# Genesis.net
KiCad netlist of a schematic drawn in EAGLE
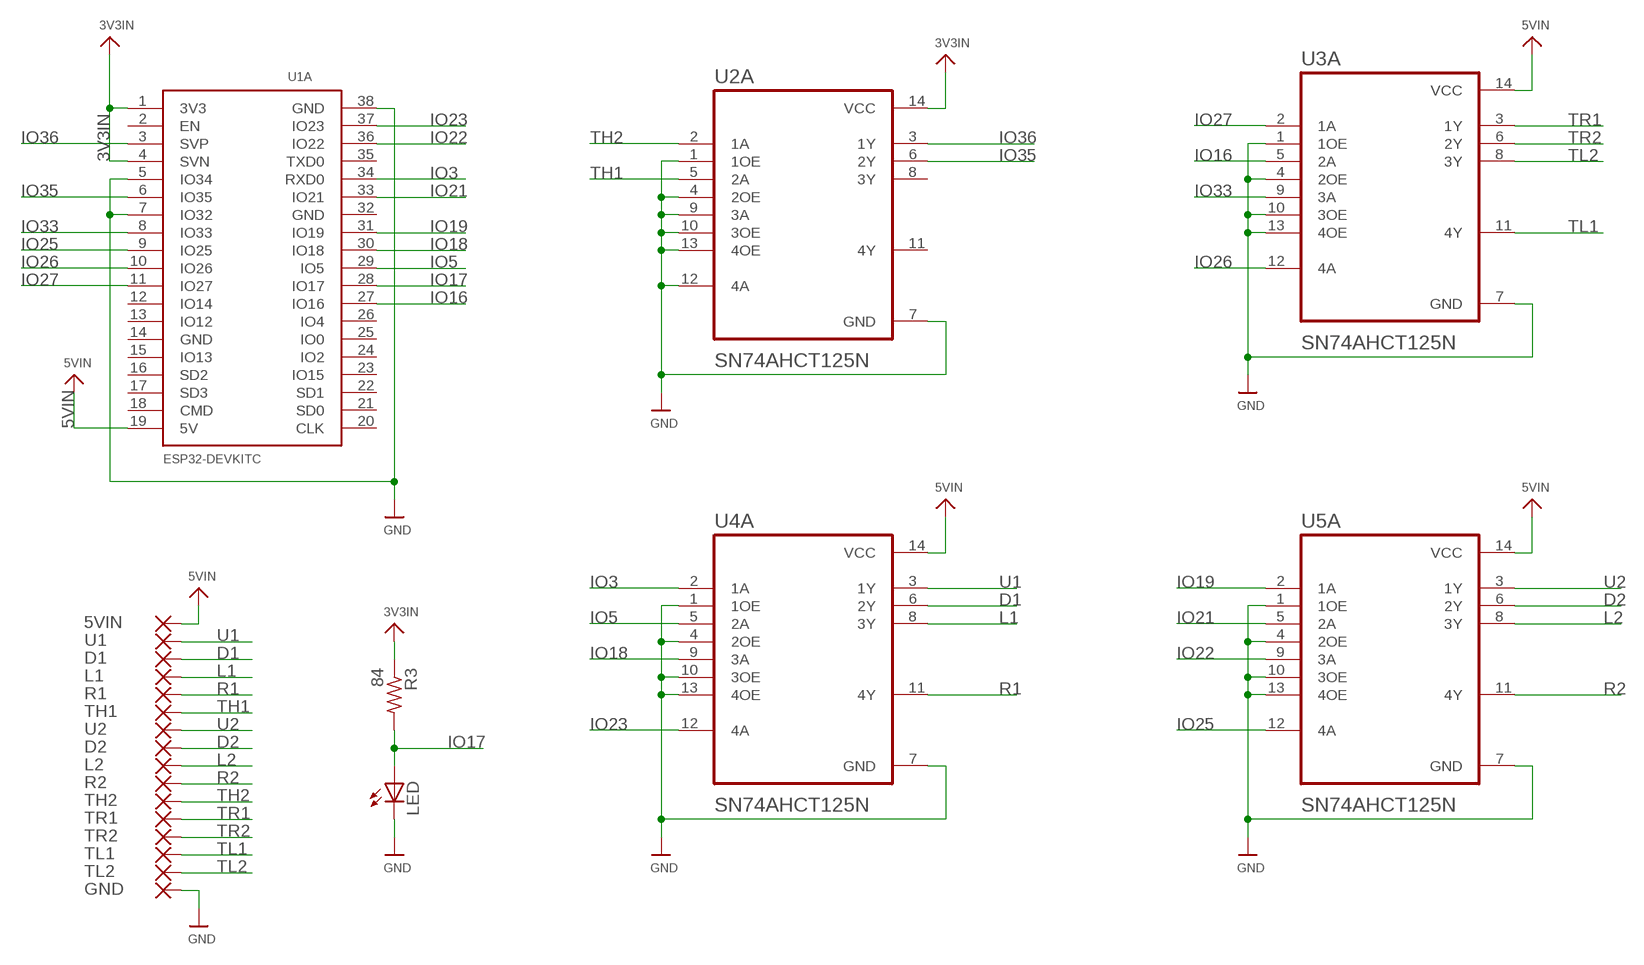
[diagram p0: schematic, sheet 1]

(export (version "E")
  (design (tool "Eeschema 10.0.6"))
  (components
    (comp (ref "5VIN")
      (value "SMD5")
      (footprint "eagle-import:SMD2,54-5,08")
      (libsource (lib "eagle-import") (part "SMD5"))
    )
    (comp (ref "D1")
      (value "SMD5")
      (footprint "eagle-import:SMD2,54-5,08")
      (libsource (lib "eagle-import") (part "SMD5"))
    )
    (comp (ref "D2")
      (value "SMD5")
      (footprint "eagle-import:SMD2,54-5,08")
      (libsource (lib "eagle-import") (part "SMD5"))
    )
    (comp (ref "GND")
      (value "SMD5")
      (footprint "eagle-import:SMD2,54-5,08")
      (libsource (lib "eagle-import") (part "SMD5"))
    )
    (comp (ref "L1")
      (value "SMD5")
      (footprint "eagle-import:SMD2,54-5,08")
      (libsource (lib "eagle-import") (part "SMD5"))
    )
    (comp (ref "L2")
      (value "SMD5")
      (footprint "eagle-import:SMD2,54-5,08")
      (libsource (lib "eagle-import") (part "SMD5"))
    )
    (comp (ref "LED")
      (value "LEDCHIPLED_1206")
      (footprint "eagle-import:CHIPLED_1206")
      (libsource (lib "eagle-import") (part "LEDCHIPLED_1206"))
    )
    (comp (ref "R1")
      (value "SMD5")
      (footprint "eagle-import:SMD2,54-5,08")
      (libsource (lib "eagle-import") (part "SMD5"))
    )
    (comp (ref "R2")
      (value "SMD5")
      (footprint "eagle-import:SMD2,54-5,08")
      (libsource (lib "eagle-import") (part "SMD5"))
    )
    (comp (ref "R3")
      (value "84")
      (footprint "eagle-import:R1206")
      (libsource (lib "eagle-import") (part "R-US_R1206"))
    )
    (comp (ref "TH1")
      (value "SMD5")
      (footprint "eagle-import:SMD2,54-5,08")
      (libsource (lib "eagle-import") (part "SMD5"))
    )
    (comp (ref "TH2")
      (value "SMD5")
      (footprint "eagle-import:SMD2,54-5,08")
      (libsource (lib "eagle-import") (part "SMD5"))
    )
    (comp (ref "TL1")
      (value "SMD5")
      (footprint "eagle-import:SMD2,54-5,08")
      (libsource (lib "eagle-import") (part "SMD5"))
    )
    (comp (ref "TL2")
      (value "SMD5")
      (footprint "eagle-import:SMD2,54-5,08")
      (libsource (lib "eagle-import") (part "SMD5"))
    )
    (comp (ref "TR1")
      (value "SMD5")
      (footprint "eagle-import:SMD2,54-5,08")
      (libsource (lib "eagle-import") (part "SMD5"))
    )
    (comp (ref "TR2")
      (value "SMD5")
      (footprint "eagle-import:SMD2,54-5,08")
      (libsource (lib "eagle-import") (part "SMD5"))
    )
    (comp (ref "U1")
      (value "SMD5")
      (footprint "eagle-import:SMD2,54-5,08")
      (libsource (lib "eagle-import") (part "SMD5"))
    )
    (comp (ref "U1A")
      (value "ESP32DEVKITC")
      (footprint "eagle-import:ESP32-DEVKITC")
      (libsource (lib "eagle-import") (part "ESP32DEVKITC"))
    )
    (comp (ref "U2")
      (value "SMD5")
      (footprint "eagle-import:SMD2,54-5,08")
      (libsource (lib "eagle-import") (part "SMD5"))
    )
    (comp (ref "U2A")
      (value "SN74AHCT125N")
      (footprint "eagle-import:DIP794W45P254L1969H508Q14")
      (fields (field (name "MF") "Texas Instruments"))
      (libsource (lib "eagle-import") (part "SN74AHCT125N"))
    )
    (comp (ref "U3A")
      (value "SN74AHCT125N")
      (footprint "eagle-import:DIP794W45P254L1969H508Q14")
      (fields (field (name "MF") "Texas Instruments"))
      (libsource (lib "eagle-import") (part "SN74AHCT125N"))
    )
    (comp (ref "U4A")
      (value "SN74AHCT125N")
      (footprint "eagle-import:DIP794W45P254L1969H508Q14")
      (fields (field (name "MF") "Texas Instruments"))
      (libsource (lib "eagle-import") (part "SN74AHCT125N"))
    )
    (comp (ref "U5A")
      (value "SN74AHCT125N")
      (footprint "eagle-import:DIP794W45P254L1969H508Q14")
      (fields (field (name "MF") "Texas Instruments"))
      (libsource (lib "eagle-import") (part "SN74AHCT125N"))
    )
  )
  (nets
    (net (code "1") (name "/D1") (class "Default")
      (node (ref "D1") (pin "1") (pinfunction "P_1") (pintype "passive"))
      (node (ref "U4A") (pin "6") (pinfunction "2Y_6") (pintype "output"))
    )
    (net (code "2") (name "/D2") (class "Default")
      (node (ref "D2") (pin "1") (pinfunction "P_1") (pintype "passive"))
      (node (ref "U5A") (pin "6") (pinfunction "2Y_6") (pintype "output"))
    )
    (net (code "3") (name "/IO3") (class "Default")
      (node (ref "U1A") (pin "34") (pinfunction "RXD0_34") (pintype "bidirectional"))
      (node (ref "U4A") (pin "2") (pinfunction "1A_2") (pintype "input"))
    )
    (net (code "4") (name "/IO5") (class "Default")
      (node (ref "U1A") (pin "29") (pinfunction "IO5_29") (pintype "bidirectional"))
      (node (ref "U4A") (pin "5") (pinfunction "2A_5") (pintype "input"))
    )
    (net (code "5") (name "/IO16") (class "Default")
      (node (ref "U1A") (pin "27") (pinfunction "IO16_27") (pintype "bidirectional"))
      (node (ref "U3A") (pin "5") (pinfunction "2A_5") (pintype "input"))
    )
    (net (code "6") (name "/IO17") (class "Default")
      (node (ref "LED") (pin "A") (pinfunction "A_A") (pintype "passive"))
      (node (ref "R3") (pin "2") (pinfunction "2_2") (pintype "passive"))
      (node (ref "U1A") (pin "28") (pinfunction "IO17_28") (pintype "bidirectional"))
    )
    (net (code "7") (name "/IO18") (class "Default")
      (node (ref "U1A") (pin "30") (pinfunction "IO18_30") (pintype "bidirectional"))
      (node (ref "U4A") (pin "9") (pinfunction "3A_9") (pintype "input"))
    )
    (net (code "8") (name "/IO19") (class "Default")
      (node (ref "U1A") (pin "31") (pinfunction "IO19_31") (pintype "bidirectional"))
      (node (ref "U5A") (pin "2") (pinfunction "1A_2") (pintype "input"))
    )
    (net (code "9") (name "/IO21") (class "Default")
      (node (ref "U1A") (pin "33") (pinfunction "IO21_33") (pintype "bidirectional"))
      (node (ref "U5A") (pin "5") (pinfunction "2A_5") (pintype "input"))
    )
    (net (code "10") (name "/IO22") (class "Default")
      (node (ref "U1A") (pin "36") (pinfunction "IO22_36") (pintype "bidirectional"))
      (node (ref "U5A") (pin "9") (pinfunction "3A_9") (pintype "input"))
    )
    (net (code "11") (name "/IO23") (class "Default")
      (node (ref "U1A") (pin "37") (pinfunction "IO23_37") (pintype "bidirectional"))
      (node (ref "U4A") (pin "12") (pinfunction "4A_12") (pintype "bidirectional"))
    )
    (net (code "12") (name "/IO25") (class "Default")
      (node (ref "U1A") (pin "9") (pinfunction "IO25_9") (pintype "bidirectional"))
      (node (ref "U5A") (pin "12") (pinfunction "4A_12") (pintype "bidirectional"))
    )
    (net (code "13") (name "/IO26") (class "Default")
      (node (ref "U1A") (pin "10") (pinfunction "IO26_10") (pintype "bidirectional"))
      (node (ref "U3A") (pin "12") (pinfunction "4A_12") (pintype "bidirectional"))
    )
    (net (code "14") (name "/IO27") (class "Default")
      (node (ref "U1A") (pin "11") (pinfunction "IO27_11") (pintype "bidirectional"))
      (node (ref "U3A") (pin "2") (pinfunction "1A_2") (pintype "input"))
    )
    (net (code "15") (name "/IO33") (class "Default")
      (node (ref "U1A") (pin "8") (pinfunction "IO33_8") (pintype "bidirectional"))
      (node (ref "U3A") (pin "9") (pinfunction "3A_9") (pintype "input"))
    )
    (net (code "16") (name "/IO35") (class "Default")
      (node (ref "U1A") (pin "6") (pinfunction "IO35_6") (pintype "bidirectional"))
      (node (ref "U2A") (pin "6") (pinfunction "2Y_6") (pintype "output"))
    )
    (net (code "17") (name "/IO36") (class "Default")
      (node (ref "U1A") (pin "3") (pinfunction "SVP_3") (pintype "bidirectional"))
      (node (ref "U2A") (pin "3") (pinfunction "1Y_3") (pintype "output"))
    )
    (net (code "18") (name "/L1") (class "Default")
      (node (ref "L1") (pin "1") (pinfunction "P_1") (pintype "passive"))
      (node (ref "U4A") (pin "8") (pinfunction "3Y_8") (pintype "output"))
    )
    (net (code "19") (name "/L2") (class "Default")
      (node (ref "L2") (pin "1") (pinfunction "P_1") (pintype "passive"))
      (node (ref "U5A") (pin "8") (pinfunction "3Y_8") (pintype "output"))
    )
    (net (code "20") (name "/R1") (class "Default")
      (node (ref "R1") (pin "1") (pinfunction "P_1") (pintype "passive"))
      (node (ref "U4A") (pin "11") (pinfunction "4Y_11") (pintype "output"))
    )
    (net (code "21") (name "/R2") (class "Default")
      (node (ref "R2") (pin "1") (pinfunction "P_1") (pintype "passive"))
      (node (ref "U5A") (pin "11") (pinfunction "4Y_11") (pintype "output"))
    )
    (net (code "22") (name "/TH1") (class "Default")
      (node (ref "TH1") (pin "1") (pinfunction "P_1") (pintype "passive"))
      (node (ref "U2A") (pin "5") (pinfunction "2A_5") (pintype "input"))
    )
    (net (code "23") (name "/TH2") (class "Default")
      (node (ref "TH2") (pin "1") (pinfunction "P_1") (pintype "passive"))
      (node (ref "U2A") (pin "2") (pinfunction "1A_2") (pintype "input"))
    )
    (net (code "24") (name "/TL1") (class "Default")
      (node (ref "TL1") (pin "1") (pinfunction "P_1") (pintype "passive"))
      (node (ref "U3A") (pin "11") (pinfunction "4Y_11") (pintype "output"))
    )
    (net (code "25") (name "/TL2") (class "Default")
      (node (ref "TL2") (pin "1") (pinfunction "P_1") (pintype "passive"))
      (node (ref "U3A") (pin "8") (pinfunction "3Y_8") (pintype "output"))
    )
    (net (code "26") (name "/TR1") (class "Default")
      (node (ref "TR1") (pin "1") (pinfunction "P_1") (pintype "passive"))
      (node (ref "U3A") (pin "3") (pinfunction "1Y_3") (pintype "output"))
    )
    (net (code "27") (name "/TR2") (class "Default")
      (node (ref "TR2") (pin "1") (pinfunction "P_1") (pintype "passive"))
      (node (ref "U3A") (pin "6") (pinfunction "2Y_6") (pintype "output"))
    )
    (net (code "28") (name "/U1") (class "Default")
      (node (ref "U1") (pin "1") (pinfunction "P_1") (pintype "passive"))
      (node (ref "U4A") (pin "3") (pinfunction "1Y_3") (pintype "output"))
    )
    (net (code "29") (name "/U2") (class "Default")
      (node (ref "U2") (pin "1") (pinfunction "P_1") (pintype "passive"))
      (node (ref "U5A") (pin "3") (pinfunction "1Y_3") (pintype "output"))
    )
    (net (code "30") (name "3V3IN") (class "Default")
      (node (ref "R3") (pin "1") (pinfunction "1_1") (pintype "passive"))
      (node (ref "U1A") (pin "1") (pinfunction "3V3_1") (pintype "bidirectional"))
      (node (ref "U1A") (pin "4") (pinfunction "SVN_4") (pintype "bidirectional"))
      (node (ref "U2A") (pin "14") (pinfunction "VCC_14") (pintype "power_in"))
    )
    (net (code "31") (name "5VIN") (class "Default")
      (node (ref "5VIN") (pin "1") (pinfunction "P_1") (pintype "passive"))
      (node (ref "U1A") (pin "19") (pinfunction "5V_19") (pintype "bidirectional"))
      (node (ref "U3A") (pin "14") (pinfunction "VCC_14") (pintype "power_in"))
      (node (ref "U4A") (pin "14") (pinfunction "VCC_14") (pintype "power_in"))
      (node (ref "U5A") (pin "14") (pinfunction "VCC_14") (pintype "power_in"))
    )
    (net (code "32") (name "GND") (class "Default")
      (node (ref "GND") (pin "1") (pinfunction "P_1") (pintype "passive"))
      (node (ref "LED") (pin "C") (pinfunction "C_C") (pintype "passive"))
      (node (ref "U1A") (pin "38") (pinfunction "GND_38") (pintype "bidirectional"))
      (node (ref "U1A") (pin "5") (pinfunction "IO34_5") (pintype "bidirectional"))
      (node (ref "U1A") (pin "7") (pinfunction "IO32_7") (pintype "bidirectional"))
      (node (ref "U2A") (pin "1") (pinfunction "1OE_1") (pintype "input"))
      (node (ref "U2A") (pin "10") (pinfunction "3OE_10") (pintype "input"))
      (node (ref "U2A") (pin "12") (pinfunction "4A_12") (pintype "bidirectional"))
      (node (ref "U2A") (pin "13") (pinfunction "4OE_13") (pintype "input"))
      (node (ref "U2A") (pin "4") (pinfunction "2OE_4") (pintype "input"))
      (node (ref "U2A") (pin "7") (pinfunction "GND_7") (pintype "power_in"))
      (node (ref "U2A") (pin "9") (pinfunction "3A_9") (pintype "input"))
      (node (ref "U3A") (pin "1") (pinfunction "1OE_1") (pintype "input"))
      (node (ref "U3A") (pin "10") (pinfunction "3OE_10") (pintype "input"))
      (node (ref "U3A") (pin "13") (pinfunction "4OE_13") (pintype "input"))
      (node (ref "U3A") (pin "4") (pinfunction "2OE_4") (pintype "input"))
      (node (ref "U3A") (pin "7") (pinfunction "GND_7") (pintype "power_in"))
      (node (ref "U4A") (pin "1") (pinfunction "1OE_1") (pintype "input"))
      (node (ref "U4A") (pin "10") (pinfunction "3OE_10") (pintype "input"))
      (node (ref "U4A") (pin "13") (pinfunction "4OE_13") (pintype "input"))
      (node (ref "U4A") (pin "4") (pinfunction "2OE_4") (pintype "input"))
      (node (ref "U4A") (pin "7") (pinfunction "GND_7") (pintype "power_in"))
      (node (ref "U5A") (pin "1") (pinfunction "1OE_1") (pintype "input"))
      (node (ref "U5A") (pin "10") (pinfunction "3OE_10") (pintype "input"))
      (node (ref "U5A") (pin "13") (pinfunction "4OE_13") (pintype "input"))
      (node (ref "U5A") (pin "4") (pinfunction "2OE_4") (pintype "input"))
      (node (ref "U5A") (pin "7") (pinfunction "GND_7") (pintype "power_in"))
    )
    (net (code "33") (name "unconnected-(U1A-CLK-Pad20)") (class "Default")
      (node (ref "U1A") (pin "20") (pinfunction "CLK_20") (pintype "bidirectional"))
    )
    (net (code "34") (name "unconnected-(U1A-CMD-Pad18)") (class "Default")
      (node (ref "U1A") (pin "18") (pinfunction "CMD_18") (pintype "bidirectional"))
    )
    (net (code "35") (name "unconnected-(U1A-EN-Pad2)") (class "Default")
      (node (ref "U1A") (pin "2") (pinfunction "EN_2") (pintype "bidirectional"))
    )
    (net (code "36") (name "unconnected-(U1A-GND-Pad14)") (class "Default")
      (node (ref "U1A") (pin "14") (pinfunction "GND_14") (pintype "bidirectional"))
    )
    (net (code "37") (name "unconnected-(U1A-GND-Pad32)") (class "Default")
      (node (ref "U1A") (pin "32") (pinfunction "GND_32") (pintype "bidirectional"))
    )
    (net (code "38") (name "unconnected-(U1A-IO0-Pad25)") (class "Default")
      (node (ref "U1A") (pin "25") (pinfunction "IO0_25") (pintype "bidirectional"))
    )
    (net (code "39") (name "unconnected-(U1A-IO2-Pad24)") (class "Default")
      (node (ref "U1A") (pin "24") (pinfunction "IO2_24") (pintype "bidirectional"))
    )
    (net (code "40") (name "unconnected-(U1A-IO4-Pad26)") (class "Default")
      (node (ref "U1A") (pin "26") (pinfunction "IO4_26") (pintype "bidirectional"))
    )
    (net (code "41") (name "unconnected-(U1A-IO12-Pad13)") (class "Default")
      (node (ref "U1A") (pin "13") (pinfunction "IO12_13") (pintype "bidirectional"))
    )
    (net (code "42") (name "unconnected-(U1A-IO13-Pad15)") (class "Default")
      (node (ref "U1A") (pin "15") (pinfunction "IO13_15") (pintype "bidirectional"))
    )
    (net (code "43") (name "unconnected-(U1A-IO14-Pad12)") (class "Default")
      (node (ref "U1A") (pin "12") (pinfunction "IO14_12") (pintype "bidirectional"))
    )
    (net (code "44") (name "unconnected-(U1A-IO15-Pad23)") (class "Default")
      (node (ref "U1A") (pin "23") (pinfunction "IO15_23") (pintype "bidirectional"))
    )
    (net (code "45") (name "unconnected-(U1A-SD0-Pad21)") (class "Default")
      (node (ref "U1A") (pin "21") (pinfunction "SD0_21") (pintype "bidirectional"))
    )
    (net (code "46") (name "unconnected-(U1A-SD1-Pad22)") (class "Default")
      (node (ref "U1A") (pin "22") (pinfunction "SD1_22") (pintype "bidirectional"))
    )
    (net (code "47") (name "unconnected-(U1A-SD2-Pad16)") (class "Default")
      (node (ref "U1A") (pin "16") (pinfunction "SD2_16") (pintype "bidirectional"))
    )
    (net (code "48") (name "unconnected-(U1A-SD3-Pad17)") (class "Default")
      (node (ref "U1A") (pin "17") (pinfunction "SD3_17") (pintype "bidirectional"))
    )
    (net (code "49") (name "unconnected-(U1A-TXD0-Pad35)") (class "Default")
      (node (ref "U1A") (pin "35") (pinfunction "TXD0_35") (pintype "bidirectional"))
    )
    (net (code "50") (name "unconnected-(U2A-3Y-Pad8)") (class "Default")
      (node (ref "U2A") (pin "8") (pinfunction "3Y_8") (pintype "output"))
    )
    (net (code "51") (name "unconnected-(U2A-4Y-Pad11)") (class "Default")
      (node (ref "U2A") (pin "11") (pinfunction "4Y_11") (pintype "output"))
    )
  )
)
